# 6DoF_IMU_Module.net
KiCad netlist of a schematic drawn in EAGLE
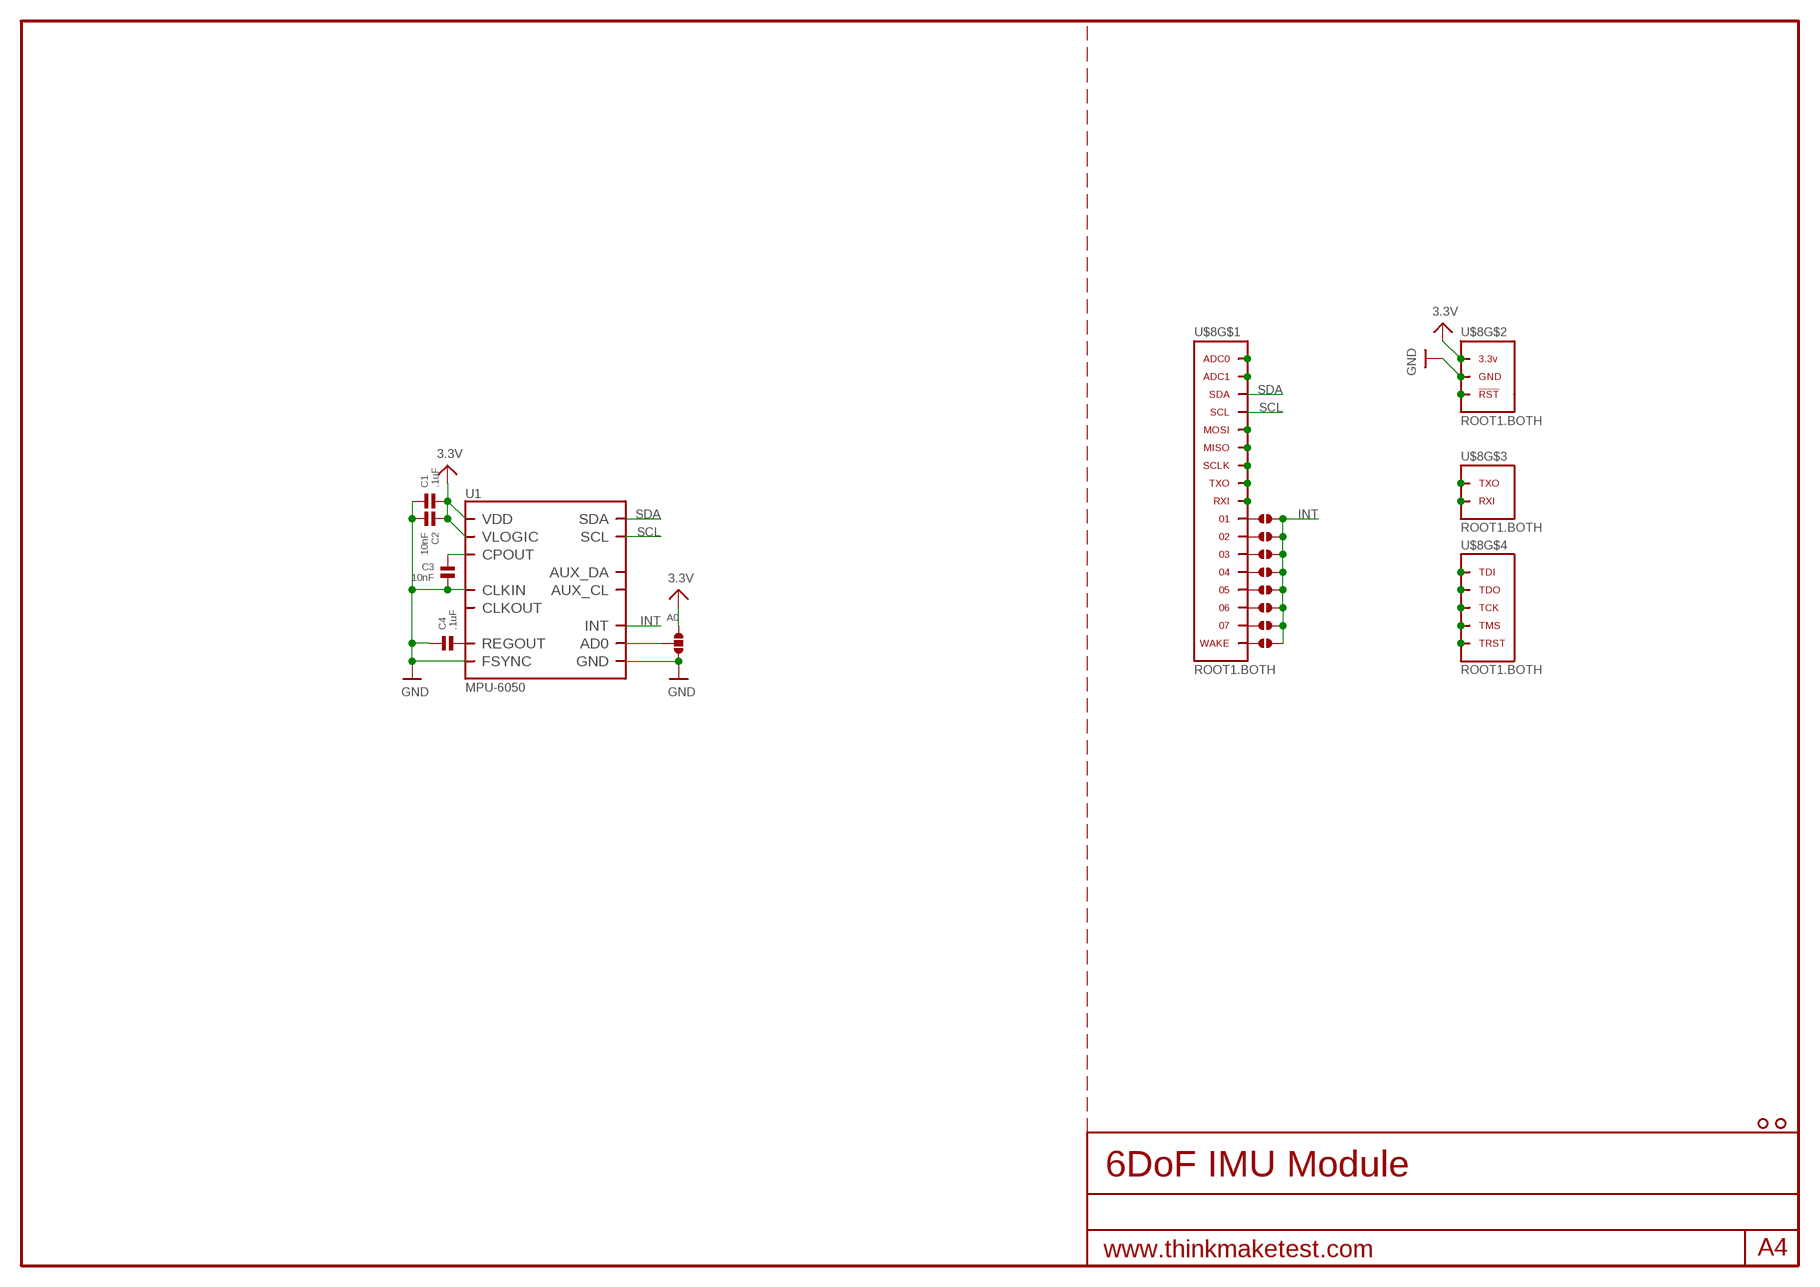
[diagram p0: schematic, sheet 1]

(export (version "E")
  (design (tool "Eeschema 10.0.6"))
  (components
    (comp (ref "A0")
      (value "SOLDERJUMPER.3.MED.23")
      (footprint "eagle-import:3.MED.23")
      (libsource (lib "eagle-import") (part "SOLDERJUMPER.3.MED.23"))
    )
    (comp (ref "C1")
      (value ".1uF")
      (footprint "eagle-import:0603")
      (libsource (lib "eagle-import") (part "CAPACITOR.0603"))
    )
    (comp (ref "C2")
      (value "10nF")
      (footprint "eagle-import:0603")
      (libsource (lib "eagle-import") (part "CAPACITOR.0603"))
    )
    (comp (ref "C3")
      (value "10nF")
      (footprint "eagle-import:0603")
      (libsource (lib "eagle-import") (part "CAPACITOR.0603"))
    )
    (comp (ref "C4")
      (value ".1uF")
      (footprint "eagle-import:0603")
      (libsource (lib "eagle-import") (part "CAPACITOR.0603"))
    )
    (comp (ref "J1")
      (value "SOLDERJUMPER.2.SML")
      (footprint "eagle-import:2.SML")
      (libsource (lib "eagle-import") (part "SOLDERJUMPER.2.SML"))
    )
    (comp (ref "J2")
      (value "SOLDERJUMPER.2.SML")
      (footprint "eagle-import:2.SML")
      (libsource (lib "eagle-import") (part "SOLDERJUMPER.2.SML"))
    )
    (comp (ref "J3")
      (value "SOLDERJUMPER.2.SML")
      (footprint "eagle-import:2.SML")
      (libsource (lib "eagle-import") (part "SOLDERJUMPER.2.SML"))
    )
    (comp (ref "J4")
      (value "SOLDERJUMPER.2.SML")
      (footprint "eagle-import:2.SML")
      (libsource (lib "eagle-import") (part "SOLDERJUMPER.2.SML"))
    )
    (comp (ref "J5")
      (value "SOLDERJUMPER.2.SML")
      (footprint "eagle-import:2.SML")
      (libsource (lib "eagle-import") (part "SOLDERJUMPER.2.SML"))
    )
    (comp (ref "J6")
      (value "SOLDERJUMPER.2.SML")
      (footprint "eagle-import:2.SML")
      (libsource (lib "eagle-import") (part "SOLDERJUMPER.2.SML"))
    )
    (comp (ref "J7")
      (value "SOLDERJUMPER.2.SML")
      (footprint "eagle-import:2.SML")
      (libsource (lib "eagle-import") (part "SOLDERJUMPER.2.SML"))
    )
    (comp (ref "J8")
      (value "SOLDERJUMPER.2.SML")
      (footprint "eagle-import:2.SML")
      (libsource (lib "eagle-import") (part "SOLDERJUMPER.2.SML"))
    )
    (comp (ref "U$4")
      (value "HOLE.#2")
      (footprint "eagle-import:#2")
      (libsource (lib "eagle-import") (part "HOLE.#2"))
    )
    (comp (ref "U$8")
      (value "ROOT1.BOTH")
      (footprint "eagle-import:ROOT1.BOTH")
      (libsource (lib "eagle-import") (part "ROOT1.BOTH"))
    )
    (comp (ref "U$12")
      (value "HOLE.#2")
      (footprint "eagle-import:#2")
      (libsource (lib "eagle-import") (part "HOLE.#2"))
    )
    (comp (ref "U1")
      (value "MPU-6050")
      (footprint "eagle-import:QFN.24.4X4")
      (libsource (lib "eagle-import") (part "MPU-6050"))
    )
  )
  (nets
    (net (code "1") (name "/INT") (class "Default")
      (node (ref "J1") (pin "2") (pinfunction "2_2") (pintype "bidirectional"))
      (node (ref "J2") (pin "2") (pinfunction "2_2") (pintype "bidirectional"))
      (node (ref "J3") (pin "2") (pinfunction "2_2") (pintype "bidirectional"))
      (node (ref "J4") (pin "2") (pinfunction "2_2") (pintype "bidirectional"))
      (node (ref "J5") (pin "2") (pinfunction "2_2") (pintype "bidirectional"))
      (node (ref "J6") (pin "2") (pinfunction "2_2") (pintype "bidirectional"))
      (node (ref "J7") (pin "2") (pinfunction "2_2") (pintype "bidirectional"))
      (node (ref "J8") (pin "2") (pinfunction "2_2") (pintype "bidirectional"))
      (node (ref "U1") (pin "12") (pinfunction "INT_12") (pintype "bidirectional"))
    )
    (net (code "2") (name "/SCL") (class "Default")
      (node (ref "U$8") (pin "SCL") (pinfunction "SCL_SCL") (pintype "bidirectional"))
      (node (ref "U$8") (pin "SCL@1") (pinfunction "SCL_SCL@1") (pintype "bidirectional"))
      (node (ref "U$8") (pin "SCL@VIA") (pinfunction "SCL_SCL@VIA") (pintype "bidirectional"))
      (node (ref "U1") (pin "23") (pinfunction "SCL_23") (pintype "bidirectional"))
    )
    (net (code "3") (name "/SDA") (class "Default")
      (node (ref "U$8") (pin "SDA") (pinfunction "SDA_SDA") (pintype "bidirectional"))
      (node (ref "U$8") (pin "SDA@1") (pinfunction "SDA_SDA@1") (pintype "bidirectional"))
      (node (ref "U$8") (pin "SDA@VIA") (pinfunction "SDA_SDA@VIA") (pintype "bidirectional"))
      (node (ref "U1") (pin "24") (pinfunction "SDA_24") (pintype "bidirectional"))
    )
    (net (code "4") (name "3.3V") (class "Default")
      (node (ref "A0") (pin "1") (pinfunction "1_1") (pintype "bidirectional"))
      (node (ref "C1") (pin "2") (pinfunction "2_2") (pintype "bidirectional"))
      (node (ref "C2") (pin "1") (pinfunction "1_1") (pintype "bidirectional"))
      (node (ref "U$8") (pin "3.3V@1") (pinfunction "3.3V_3.3V@1") (pintype "bidirectional"))
      (node (ref "U$8") (pin "3.3V@10") (pinfunction "3.3V_3.3V@10") (pintype "bidirectional"))
      (node (ref "U$8") (pin "3.3V@11") (pinfunction "3.3V_3.3V@11") (pintype "bidirectional"))
      (node (ref "U$8") (pin "3.3V@12") (pinfunction "3.3V_3.3V@12") (pintype "bidirectional"))
      (node (ref "U$8") (pin "3.3V@13") (pinfunction "3.3V_3.3V@13") (pintype "bidirectional"))
      (node (ref "U$8") (pin "3.3V@14") (pinfunction "3.3V_3.3V@14") (pintype "bidirectional"))
      (node (ref "U$8") (pin "3.3V@15") (pinfunction "3.3V_3.3V@15") (pintype "bidirectional"))
      (node (ref "U$8") (pin "3.3V@16") (pinfunction "3.3V_3.3V@16") (pintype "bidirectional"))
      (node (ref "U$8") (pin "3.3V@17") (pinfunction "3.3V_3.3V@17") (pintype "bidirectional"))
      (node (ref "U$8") (pin "3.3V@18") (pinfunction "3.3V_3.3V@18") (pintype "bidirectional"))
      (node (ref "U$8") (pin "3.3V@19") (pinfunction "3.3V_3.3V@19") (pintype "bidirectional"))
      (node (ref "U$8") (pin "3.3V@2") (pinfunction "3.3V_3.3V@2") (pintype "bidirectional"))
      (node (ref "U$8") (pin "3.3V@20") (pinfunction "3.3V_3.3V@20") (pintype "bidirectional"))
      (node (ref "U$8") (pin "3.3V@21") (pinfunction "3.3V_3.3V@21") (pintype "bidirectional"))
      (node (ref "U$8") (pin "3.3V@22") (pinfunction "3.3V_3.3V@22") (pintype "bidirectional"))
      (node (ref "U$8") (pin "3.3V@23") (pinfunction "3.3V_3.3V@23") (pintype "bidirectional"))
      (node (ref "U$8") (pin "3.3V@24") (pinfunction "3.3V_3.3V@24") (pintype "bidirectional"))
      (node (ref "U$8") (pin "3.3V@3") (pinfunction "3.3V_3.3V@3") (pintype "bidirectional"))
      (node (ref "U$8") (pin "3.3V@4") (pinfunction "3.3V_3.3V@4") (pintype "bidirectional"))
      (node (ref "U$8") (pin "3.3V@5") (pinfunction "3.3V_3.3V@5") (pintype "bidirectional"))
      (node (ref "U$8") (pin "3.3V@6") (pinfunction "3.3V_3.3V@6") (pintype "bidirectional"))
      (node (ref "U$8") (pin "3.3V@7") (pinfunction "3.3V_3.3V@7") (pintype "bidirectional"))
      (node (ref "U$8") (pin "3.3V@8") (pinfunction "3.3V_3.3V@8") (pintype "bidirectional"))
      (node (ref "U$8") (pin "3.3V@9") (pinfunction "3.3V_3.3V@9") (pintype "bidirectional"))
      (node (ref "U$8") (pin "3.3V@VIA") (pinfunction "3.3V_3.3V@VIA") (pintype "bidirectional"))
      (node (ref "U1") (pin "13") (pinfunction "VDD_13") (pintype "bidirectional"))
      (node (ref "U1") (pin "8") (pinfunction "VLOGIC_8") (pintype "bidirectional"))
    )
    (net (code "5") (name "GND") (class "Default")
      (node (ref "A0") (pin "3") (pinfunction "3_3") (pintype "bidirectional"))
      (node (ref "C1") (pin "1") (pinfunction "1_1") (pintype "bidirectional"))
      (node (ref "C2") (pin "2") (pinfunction "2_2") (pintype "bidirectional"))
      (node (ref "C3") (pin "2") (pinfunction "2_2") (pintype "bidirectional"))
      (node (ref "C4") (pin "1") (pinfunction "1_1") (pintype "bidirectional"))
      (node (ref "U$8") (pin "GND@1") (pinfunction "GND_GND@1") (pintype "bidirectional"))
      (node (ref "U$8") (pin "GND@10") (pinfunction "GND_GND@10") (pintype "bidirectional"))
      (node (ref "U$8") (pin "GND@11") (pinfunction "GND_GND@11") (pintype "bidirectional"))
      (node (ref "U$8") (pin "GND@12") (pinfunction "GND_GND@12") (pintype "bidirectional"))
      (node (ref "U$8") (pin "GND@13") (pinfunction "GND_GND@13") (pintype "bidirectional"))
      (node (ref "U$8") (pin "GND@14") (pinfunction "GND_GND@14") (pintype "bidirectional"))
      (node (ref "U$8") (pin "GND@15") (pinfunction "GND_GND@15") (pintype "bidirectional"))
      (node (ref "U$8") (pin "GND@16") (pinfunction "GND_GND@16") (pintype "bidirectional"))
      (node (ref "U$8") (pin "GND@17") (pinfunction "GND_GND@17") (pintype "bidirectional"))
      (node (ref "U$8") (pin "GND@18") (pinfunction "GND_GND@18") (pintype "bidirectional"))
      (node (ref "U$8") (pin "GND@19") (pinfunction "GND_GND@19") (pintype "bidirectional"))
      (node (ref "U$8") (pin "GND@2") (pinfunction "GND_GND@2") (pintype "bidirectional"))
      (node (ref "U$8") (pin "GND@20") (pinfunction "GND_GND@20") (pintype "bidirectional"))
      (node (ref "U$8") (pin "GND@21") (pinfunction "GND_GND@21") (pintype "bidirectional"))
      (node (ref "U$8") (pin "GND@22") (pinfunction "GND_GND@22") (pintype "bidirectional"))
      (node (ref "U$8") (pin "GND@23") (pinfunction "GND_GND@23") (pintype "bidirectional"))
      (node (ref "U$8") (pin "GND@24") (pinfunction "GND_GND@24") (pintype "bidirectional"))
      (node (ref "U$8") (pin "GND@25") (pinfunction "GND_GND@25") (pintype "bidirectional"))
      (node (ref "U$8") (pin "GND@26") (pinfunction "GND_GND@26") (pintype "bidirectional"))
      (node (ref "U$8") (pin "GND@3") (pinfunction "GND_GND@3") (pintype "bidirectional"))
      (node (ref "U$8") (pin "GND@4") (pinfunction "GND_GND@4") (pintype "bidirectional"))
      (node (ref "U$8") (pin "GND@5") (pinfunction "GND_GND@5") (pintype "bidirectional"))
      (node (ref "U$8") (pin "GND@6") (pinfunction "GND_GND@6") (pintype "bidirectional"))
      (node (ref "U$8") (pin "GND@7") (pinfunction "GND_GND@7") (pintype "bidirectional"))
      (node (ref "U$8") (pin "GND@8") (pinfunction "GND_GND@8") (pintype "bidirectional"))
      (node (ref "U$8") (pin "GND@9") (pinfunction "GND_GND@9") (pintype "bidirectional"))
      (node (ref "U$8") (pin "GND@VIA") (pinfunction "GND_GND@VIA") (pintype "bidirectional"))
      (node (ref "U1") (pin "1") (pinfunction "CLKIN_1") (pintype "bidirectional"))
      (node (ref "U1") (pin "11") (pinfunction "FSYNC_11") (pintype "bidirectional"))
      (node (ref "U1") (pin "18") (pinfunction "GND_18") (pintype "bidirectional"))
    )
    (net (code "6") (name "Net-(J1-Pad1)") (class "Default")
      (node (ref "J1") (pin "1") (pinfunction "1_1") (pintype "bidirectional"))
      (node (ref "U$8") (pin "01") (pinfunction "01_01") (pintype "bidirectional"))
      (node (ref "U$8") (pin "01@1") (pinfunction "01_01@1") (pintype "bidirectional"))
      (node (ref "U$8") (pin "01@VIA") (pinfunction "01_01@VIA") (pintype "bidirectional"))
    )
    (net (code "7") (name "Net-(J2-Pad1)") (class "Default")
      (node (ref "J2") (pin "1") (pinfunction "1_1") (pintype "bidirectional"))
      (node (ref "U$8") (pin "02") (pinfunction "02_02") (pintype "bidirectional"))
      (node (ref "U$8") (pin "02@1") (pinfunction "02_02@1") (pintype "bidirectional"))
      (node (ref "U$8") (pin "02@VIA") (pinfunction "02_02@VIA") (pintype "bidirectional"))
    )
    (net (code "8") (name "Net-(J3-Pad1)") (class "Default")
      (node (ref "J3") (pin "1") (pinfunction "1_1") (pintype "bidirectional"))
      (node (ref "U$8") (pin "03") (pinfunction "03_03") (pintype "bidirectional"))
      (node (ref "U$8") (pin "03@1") (pinfunction "03_03@1") (pintype "bidirectional"))
      (node (ref "U$8") (pin "03@VIA") (pinfunction "03_03@VIA") (pintype "bidirectional"))
    )
    (net (code "9") (name "Net-(J4-Pad1)") (class "Default")
      (node (ref "J4") (pin "1") (pinfunction "1_1") (pintype "bidirectional"))
      (node (ref "U$8") (pin "04") (pinfunction "04_04") (pintype "bidirectional"))
      (node (ref "U$8") (pin "04@1") (pinfunction "04_04@1") (pintype "bidirectional"))
      (node (ref "U$8") (pin "04@VIA") (pinfunction "04_04@VIA") (pintype "bidirectional"))
    )
    (net (code "10") (name "Net-(J5-Pad1)") (class "Default")
      (node (ref "J5") (pin "1") (pinfunction "1_1") (pintype "bidirectional"))
      (node (ref "U$8") (pin "05") (pinfunction "05_05") (pintype "bidirectional"))
      (node (ref "U$8") (pin "05@1") (pinfunction "05_05@1") (pintype "bidirectional"))
      (node (ref "U$8") (pin "05@VIA") (pinfunction "05_05@VIA") (pintype "bidirectional"))
    )
    (net (code "11") (name "Net-(J6-Pad1)") (class "Default")
      (node (ref "J6") (pin "1") (pinfunction "1_1") (pintype "bidirectional"))
      (node (ref "U$8") (pin "06") (pinfunction "06_06") (pintype "bidirectional"))
      (node (ref "U$8") (pin "06@1") (pinfunction "06_06@1") (pintype "bidirectional"))
      (node (ref "U$8") (pin "06@VIA") (pinfunction "06_06@VIA") (pintype "bidirectional"))
    )
    (net (code "12") (name "Net-(J7-Pad1)") (class "Default")
      (node (ref "J7") (pin "1") (pinfunction "1_1") (pintype "bidirectional"))
      (node (ref "U$8") (pin "07") (pinfunction "07_07") (pintype "bidirectional"))
      (node (ref "U$8") (pin "07@1") (pinfunction "07_07@1") (pintype "bidirectional"))
      (node (ref "U$8") (pin "07@VIA") (pinfunction "07_07@VIA") (pintype "bidirectional"))
    )
    (net (code "13") (name "Net-(J8-Pad1)") (class "Default")
      (node (ref "J8") (pin "1") (pinfunction "1_1") (pintype "bidirectional"))
      (node (ref "U$8") (pin "WAKE") (pinfunction "WAKE_WAKE") (pintype "bidirectional"))
      (node (ref "U$8") (pin "WAKE@1") (pinfunction "WAKE_WAKE@1") (pintype "bidirectional"))
      (node (ref "U$8") (pin "WAKE@VIA") (pinfunction "WAKE_WAKE@VIA") (pintype "bidirectional"))
    )
    (net (code "14") (name "Net-(U$8-PadADC0)") (class "Default")
      (node (ref "U$8") (pin "ADC0") (pinfunction "ADC0_ADC0") (pintype "bidirectional"))
      (node (ref "U$8") (pin "ADC0@1") (pinfunction "ADC0_ADC0@1") (pintype "bidirectional"))
      (node (ref "U$8") (pin "ADC0@VIA") (pinfunction "ADC0_ADC0@VIA") (pintype "bidirectional"))
    )
    (net (code "15") (name "Net-(U$8-PadADC1)") (class "Default")
      (node (ref "U$8") (pin "ADC1") (pinfunction "ADC1_ADC1") (pintype "bidirectional"))
      (node (ref "U$8") (pin "ADC1@1") (pinfunction "ADC1_ADC1@1") (pintype "bidirectional"))
      (node (ref "U$8") (pin "ADC1@VIA") (pinfunction "ADC1_ADC1@VIA") (pintype "bidirectional"))
    )
    (net (code "16") (name "Net-(U$8-PadMISO)") (class "Default")
      (node (ref "U$8") (pin "MISO") (pinfunction "MISO_MISO") (pintype "bidirectional"))
      (node (ref "U$8") (pin "MISO@1") (pinfunction "MISO_MISO@1") (pintype "bidirectional"))
      (node (ref "U$8") (pin "MISO@VIA") (pinfunction "MISO_MISO@VIA") (pintype "bidirectional"))
    )
    (net (code "17") (name "Net-(U$8-PadMOSI)") (class "Default")
      (node (ref "U$8") (pin "MOSI") (pinfunction "MOSI_MOSI") (pintype "bidirectional"))
      (node (ref "U$8") (pin "MOSI@1") (pinfunction "MOSI_MOSI@1") (pintype "bidirectional"))
      (node (ref "U$8") (pin "MOSI@VIA") (pinfunction "MOSI_MOSI@VIA") (pintype "bidirectional"))
    )
    (net (code "18") (name "Net-(U$8-PadRXI)") (class "Default")
      (node (ref "U$8") (pin "RXI") (pinfunction "RXI_RXI") (pintype "bidirectional"))
      (node (ref "U$8") (pin "RXI@1") (pinfunction "RXI_RXI@1") (pintype "bidirectional"))
      (node (ref "U$8") (pin "RXI@VIA") (pinfunction "RXI_RXI@VIA") (pintype "bidirectional"))
    )
    (net (code "19") (name "Net-(U$8-PadSCLK)") (class "Default")
      (node (ref "U$8") (pin "SCLK") (pinfunction "SCLK_SCLK") (pintype "bidirectional"))
      (node (ref "U$8") (pin "SCLK@1") (pinfunction "SCLK_SCLK@1") (pintype "bidirectional"))
      (node (ref "U$8") (pin "SCLK@VIA") (pinfunction "SCLK_SCLK@VIA") (pintype "bidirectional"))
    )
    (net (code "20") (name "Net-(U$8-PadTCK)") (class "Default")
      (node (ref "U$8") (pin "TCK") (pinfunction "TCK_TCK") (pintype "bidirectional"))
      (node (ref "U$8") (pin "TCK@1") (pinfunction "TCK_TCK@1") (pintype "bidirectional"))
      (node (ref "U$8") (pin "TCK@VIA") (pinfunction "TCK_TCK@VIA") (pintype "bidirectional"))
    )
    (net (code "21") (name "Net-(U$8-PadTDI)") (class "Default")
      (node (ref "U$8") (pin "TDI") (pinfunction "TDI_TDI") (pintype "bidirectional"))
      (node (ref "U$8") (pin "TDI@1") (pinfunction "TDI_TDI@1") (pintype "bidirectional"))
      (node (ref "U$8") (pin "TDI@VIA") (pinfunction "TDI_TDI@VIA") (pintype "bidirectional"))
    )
    (net (code "22") (name "Net-(U$8-PadTDO)") (class "Default")
      (node (ref "U$8") (pin "TDO") (pinfunction "TDO_TDO") (pintype "bidirectional"))
      (node (ref "U$8") (pin "TDO@1") (pinfunction "TDO_TDO@1") (pintype "bidirectional"))
      (node (ref "U$8") (pin "TDO@VIA") (pinfunction "TDO_TDO@VIA") (pintype "bidirectional"))
    )
    (net (code "23") (name "Net-(U$8-PadTMS)") (class "Default")
      (node (ref "U$8") (pin "TMS") (pinfunction "TMS_TMS") (pintype "bidirectional"))
      (node (ref "U$8") (pin "TMS@1") (pinfunction "TMS_TMS@1") (pintype "bidirectional"))
      (node (ref "U$8") (pin "TMS@VIA") (pinfunction "TMS_TMS@VIA") (pintype "bidirectional"))
    )
    (net (code "24") (name "Net-(U$8-PadTRST)") (class "Default")
      (node (ref "U$8") (pin "TRST") (pinfunction "TRST_TRST") (pintype "bidirectional"))
      (node (ref "U$8") (pin "TRST@1") (pinfunction "TRST_TRST@1") (pintype "bidirectional"))
      (node (ref "U$8") (pin "TRST@VIA") (pinfunction "TRST_TRST@VIA") (pintype "bidirectional"))
    )
    (net (code "25") (name "Net-(U$8-PadTXO)") (class "Default")
      (node (ref "U$8") (pin "TXO") (pinfunction "TXO_TXO") (pintype "bidirectional"))
      (node (ref "U$8") (pin "TXO@1") (pinfunction "TXO_TXO@1") (pintype "bidirectional"))
      (node (ref "U$8") (pin "TXO@VIA") (pinfunction "TXO_TXO@VIA") (pintype "bidirectional"))
    )
    (net (code "26") (name "Net-(U$8B-~{RST}-PadRST)") (class "Default")
      (node (ref "U$8") (pin "RST") (pinfunction "~{RST}_RST") (pintype "bidirectional"))
      (node (ref "U$8") (pin "RST@1") (pinfunction "~{RST}_RST@1") (pintype "bidirectional"))
      (node (ref "U$8") (pin "RST@VIA") (pinfunction "~{RST}_RST@VIA") (pintype "bidirectional"))
    )
    (net (code "27") (name "Net-(U$8C-RXI-PadRXI.DBG)") (class "Default")
      (node (ref "U$8") (pin "RXI.DBG") (pinfunction "RXI_RXI.DBG") (pintype "bidirectional"))
      (node (ref "U$8") (pin "RXI.DBG@1") (pinfunction "RXI_RXI.DBG@1") (pintype "bidirectional"))
      (node (ref "U$8") (pin "RXI.DBG@VIA") (pinfunction "RXI_RXI.DBG@VIA") (pintype "bidirectional"))
    )
    (net (code "28") (name "Net-(U$8C-TXO-PadTXO.DBG)") (class "Default")
      (node (ref "U$8") (pin "TXO.DBG") (pinfunction "TXO_TXO.DBG") (pintype "bidirectional"))
      (node (ref "U$8") (pin "TXO.DBG@1") (pinfunction "TXO_TXO.DBG@1") (pintype "bidirectional"))
      (node (ref "U$8") (pin "TXO.DBG@VIA") (pinfunction "TXO_TXO.DBG@VIA") (pintype "bidirectional"))
    )
    (net (code "29") (name "Net-(U1-AD0)") (class "Default")
      (node (ref "A0") (pin "2") (pinfunction "2_2") (pintype "bidirectional"))
      (node (ref "U1") (pin "9") (pinfunction "AD0_9") (pintype "bidirectional"))
    )
    (net (code "30") (name "Net-(U1-CPOUT)") (class "Default")
      (node (ref "C3") (pin "1") (pinfunction "1_1") (pintype "bidirectional"))
      (node (ref "U1") (pin "20") (pinfunction "CPOUT_20") (pintype "bidirectional"))
    )
    (net (code "31") (name "Net-(U1-REGOUT)") (class "Default")
      (node (ref "C4") (pin "2") (pinfunction "2_2") (pintype "bidirectional"))
      (node (ref "U1") (pin "10") (pinfunction "REGOUT_10") (pintype "bidirectional"))
    )
    (net (code "32") (name "unconnected-(U1-AUX_CL-Pad7)") (class "Default")
      (node (ref "U1") (pin "7") (pinfunction "AUX_CL_7") (pintype "bidirectional"))
    )
    (net (code "33") (name "unconnected-(U1-AUX_DA-Pad6)") (class "Default")
      (node (ref "U1") (pin "6") (pinfunction "AUX_DA_6") (pintype "bidirectional"))
    )
    (net (code "34") (name "unconnected-(U1-CLKOUT-Pad22)") (class "Default")
      (node (ref "U1") (pin "22") (pinfunction "CLKOUT_22") (pintype "bidirectional"))
    )
  )
)
